# IMU_V1_0.net
KiCad netlist of a schematic drawn in EAGLE
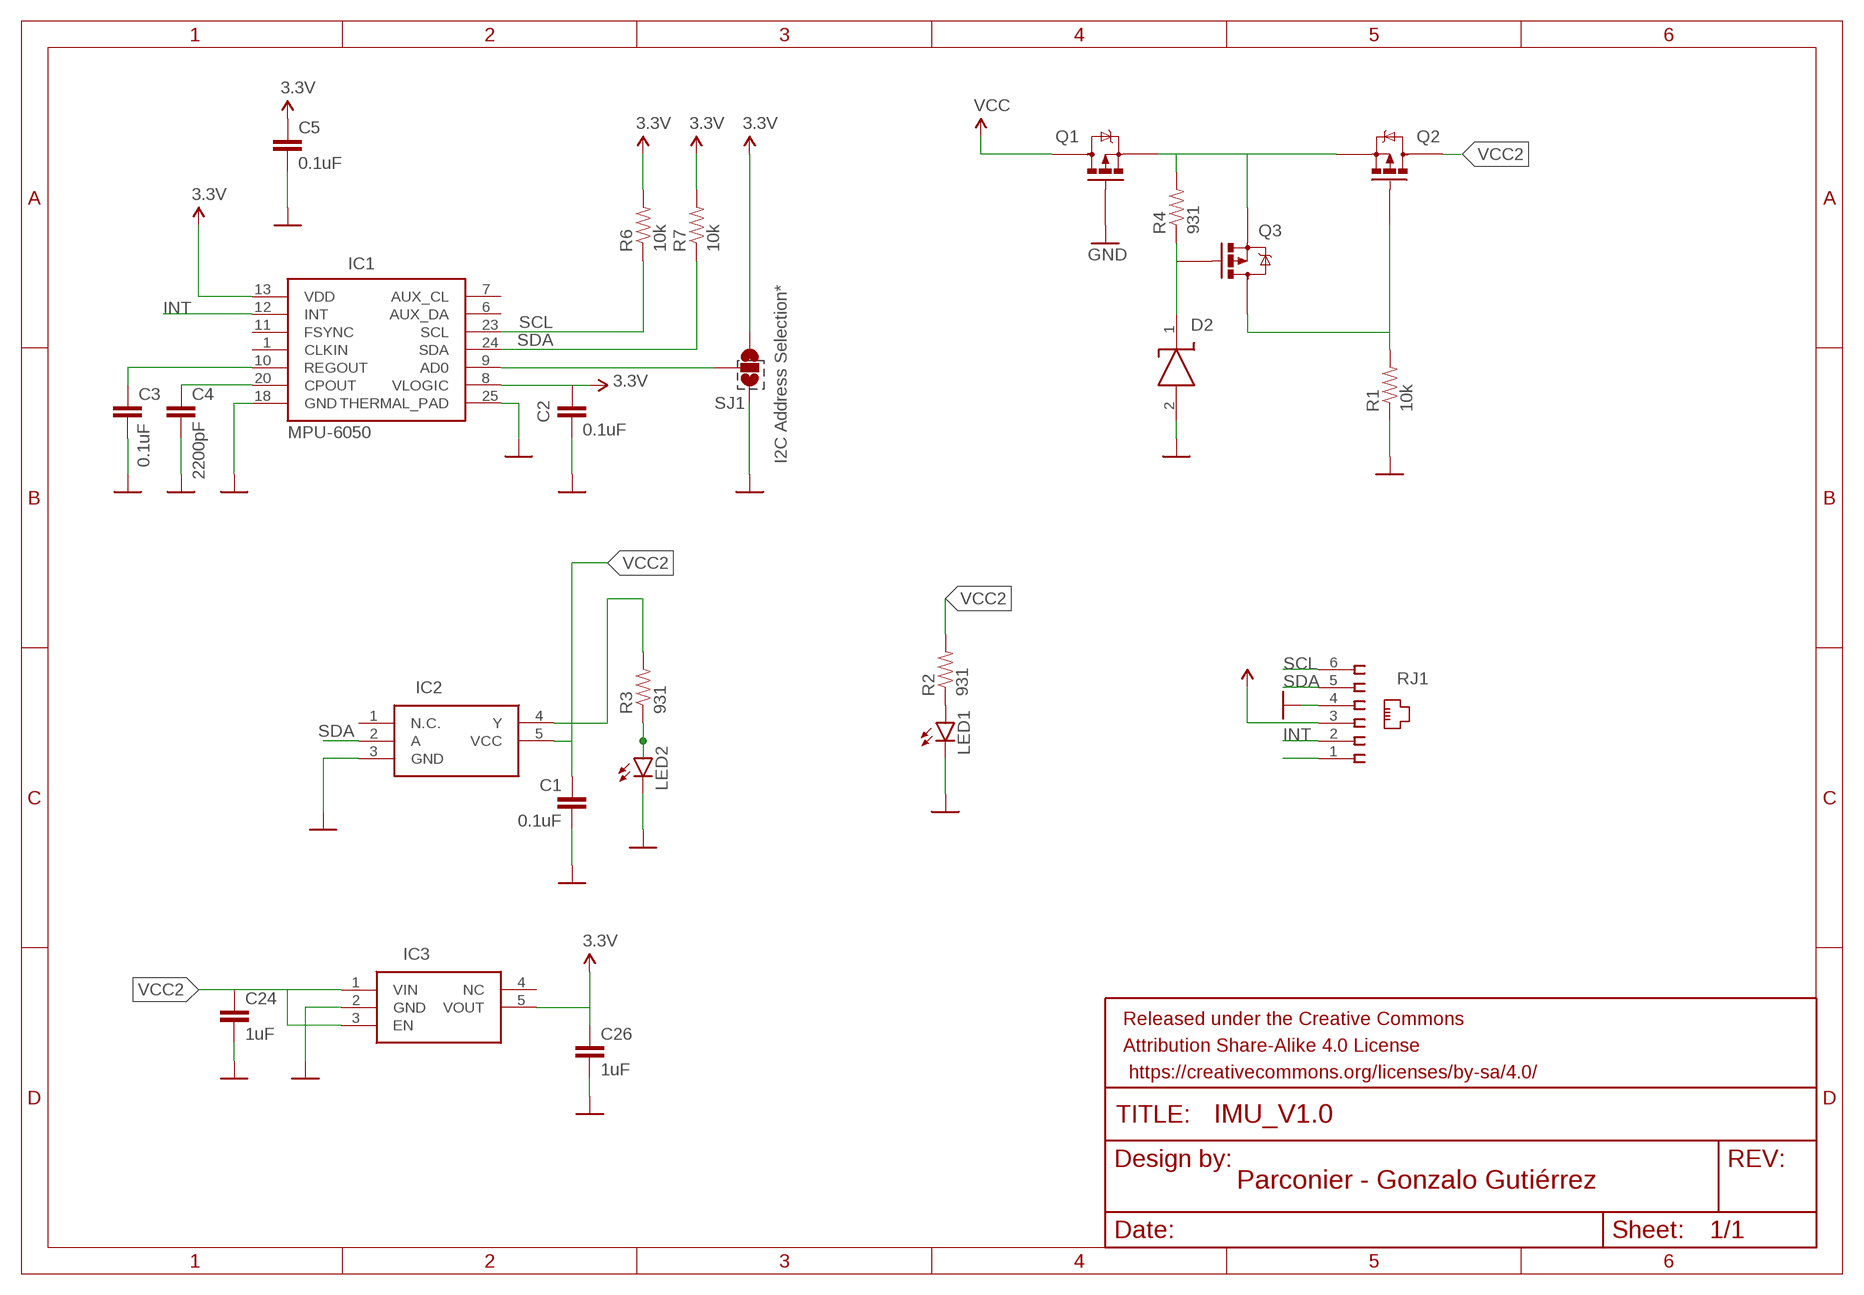
[diagram p0: schematic, sheet 1]

(export (version "E")
  (design (tool "Eeschema 10.0.6"))
  (components
    (comp (ref "C1")
      (value "0.1uF")
      (footprint "eagle-import:0402")
      (fields (field (name "MPN") "CC0402KRX5R9BB104"))
      (libsource (lib "eagle-import") (part "CAP_0402"))
    )
    (comp (ref "C2")
      (value "0.1uF")
      (footprint "eagle-import:0402")
      (fields (field (name "MPN") "CC0402KRX5R9BB104"))
      (libsource (lib "eagle-import") (part "CAP_0402"))
    )
    (comp (ref "C3")
      (value "0.1uF")
      (footprint "eagle-import:0402")
      (fields (field (name "MPN") "CC0402KRX5R9BB104"))
      (libsource (lib "eagle-import") (part "CAP_0402"))
    )
    (comp (ref "C4")
      (value "2200pF")
      (footprint "eagle-import:0402")
      (fields (field (name "MPN") "GRM155R71H222JA01D"))
      (libsource (lib "eagle-import") (part "CAP_0402"))
    )
    (comp (ref "C5")
      (value "0.1uF")
      (footprint "eagle-import:0402")
      (fields (field (name "MPN") "CC0402KRX5R9BB104"))
      (libsource (lib "eagle-import") (part "CAP_0402"))
    )
    (comp (ref "C24")
      (value "1uF")
      (footprint "eagle-import:0402")
      (fields (field (name "MPN") "CC0402ZRY5V6BB105"))
      (libsource (lib "eagle-import") (part "CAP_0402"))
    )
    (comp (ref "C26")
      (value "1uF")
      (footprint "eagle-import:0402")
      (fields (field (name "MPN") "CC0402ZRY5V6BB105"))
      (libsource (lib "eagle-import") (part "CAP_0402"))
    )
    (comp (ref "D2")
      (value "BZT52C5V1-7-F")
      (footprint "eagle-import:SOD3716X145N")
      (fields (field (name "RS_PART_NUMBER") "7384951P"))
      (libsource (lib "eagle-import") (part "BZT52C5V1-7-F"))
    )
    (comp (ref "IC1")
      (value "MPU-6050")
      (footprint "eagle-import:QFN50P400X400X95-25N")
      (fields (field (name "RS_PART_NUMBER") "8837948P"))
      (libsource (lib "eagle-import") (part "MPU-6050"))
    )
    (comp (ref "IC2")
      (value "74LVC1G14GW-Q100,1")
      (footprint "eagle-import:SOT65P212X110-5N")
      (fields (field (name "RS_PART_NUMBER") "1526474") (field (name "MPN") " 74AHC1G14GW-Q100,1"))
      (libsource (lib "eagle-import") (part "74LVC1G14GW-Q100,1"))
    )
    (comp (ref "IC3")
      (value "MIC5504-3.3YM5-TR")
      (footprint "eagle-import:SOT95P280X145-5N")
      (fields (field (name "RS_PART_NUMBER") "9113332"))
      (libsource (lib "eagle-import") (part "MIC5504-3.3YM5-TR"))
    )
    (comp (ref "LED1")
      (value "LED0603")
      (footprint "eagle-import:LED-0603")
      (fields (field (name "MPN") "LTST-C193KRKT-5A"))
      (libsource (lib "eagle-import") (part "LED0603"))
    )
    (comp (ref "LED2")
      (value "LED0603")
      (footprint "eagle-import:LED-0603")
      (fields (field (name "MPN") "LB Q39E-L2OO-35-1 "))
      (libsource (lib "eagle-import") (part "LED0603"))
    )
    (comp (ref "Q1")
      (value "RU1C002ZPTCL")
      (footprint "eagle-import:SOTFL65P210X105-3N")
      (libsource (lib "eagle-import") (part "RU1C002ZPTCL"))
    )
    (comp (ref "Q2")
      (value "RU1C002ZPTCL")
      (footprint "eagle-import:SOTFL65P210X105-3N")
      (description "ROHM - RU1C002ZPTCL - MOSFET, P-CH, -20V, -0.2A, SOT-323FL")
      (fields
        (field (name "ARROW_PART_NUMBER") "RU1C002ZPTCL")
        (field (name "HEIGHT") "1.05mm")
        (field (name "MANUFACTURER_NAME") "ROHM Semiconductor")
        (field (name "MANUFACTURER_PART_NUMBER") "RU1C002ZPTCL")
      )
      (libsource (lib "eagle-import") (part "RU1C002ZPTCL"))
    )
    (comp (ref "Q3")
      (value "RU1C002ZPTCL")
      (footprint "eagle-import:SOTFL65P210X105-3N")
      (description "ROHM - RU1C002ZPTCL - MOSFET, P-CH, -20V, -0.2A, SOT-323FL")
      (fields
        (field (name "ARROW_PART_NUMBER") "RU1C002ZPTCL")
        (field (name "HEIGHT") "1.05mm")
        (field (name "MANUFACTURER_NAME") "ROHM Semiconductor")
        (field (name "MANUFACTURER_PART_NUMBER") "RU1C002ZPTCL")
      )
      (libsource (lib "eagle-import") (part "RU1C002ZPTCL"))
    )
    (comp (ref "R1")
      (value "10k")
      (footprint "eagle-import:RESC1005X35")
      (fields (field (name "MPN") "RC0402JR-7W10KL"))
      (libsource (lib "eagle-import") (part "RES_0402"))
    )
    (comp (ref "R2")
      (value "931")
      (footprint "eagle-import:RESC1005X35")
      (fields (field (name "MPN") "RC0402FR-07931RL"))
      (libsource (lib "eagle-import") (part "RES_0402"))
    )
    (comp (ref "R3")
      (value "931")
      (footprint "eagle-import:RESC1005X35")
      (fields (field (name "MPN") "RC0402FR-07931RL"))
      (libsource (lib "eagle-import") (part "RES_0402"))
    )
    (comp (ref "R4")
      (value "931")
      (footprint "eagle-import:RESC1005X35")
      (fields (field (name "MPN") "RC0402FR-07931RL"))
      (libsource (lib "eagle-import") (part "RES_0402"))
    )
    (comp (ref "R6")
      (value "10k")
      (footprint "eagle-import:RESC1005X35")
      (fields (field (name "MPN") "RC0402JR-7W10KL"))
      (libsource (lib "eagle-import") (part "RES_0402"))
    )
    (comp (ref "R7")
      (value "10k")
      (footprint "eagle-import:RESC1005X35")
      (fields (field (name "MPN") "RC0402JR-7W10KL"))
      (libsource (lib "eagle-import") (part "RES_0402"))
    )
    (comp (ref "RJ1")
      (value "615006138421")
      (footprint "eagle-import:615006138421")
      (fields (field (name "RS_PART_NUMBER") "7350282"))
      (libsource (lib "eagle-import") (part "615006138421"))
    )
    (comp (ref "SJ1")
      (value "SOLDERJUMPER_2WAYPASTE2&3")
      (footprint "eagle-import:SJ_3_PASTE2&3")
      (libsource (lib "eagle-import") (part "SOLDERJUMPER_2WAYPASTE2&3"))
    )
  )
  (nets
    (net (code "1") (name "/INT") (class "Default")
      (node (ref "IC1") (pin "12") (pinfunction "INT_12") (pintype "bidirectional"))
      (node (ref "RJ1") (pin "2") (pinfunction "2_2") (pintype "input"))
    )
    (net (code "2") (name "/SCL") (class "Default")
      (node (ref "IC1") (pin "23") (pinfunction "SCL_23") (pintype "bidirectional"))
      (node (ref "R6") (pin "1") (pinfunction "1_1") (pintype "passive"))
      (node (ref "RJ1") (pin "6") (pinfunction "6_6") (pintype "input"))
    )
    (net (code "3") (name "/SDA") (class "Default")
      (node (ref "IC1") (pin "24") (pinfunction "SDA_24") (pintype "bidirectional"))
      (node (ref "IC2") (pin "2") (pinfunction "A_2") (pintype "bidirectional"))
      (node (ref "R7") (pin "1") (pinfunction "1_1") (pintype "passive"))
      (node (ref "RJ1") (pin "5") (pinfunction "5_5") (pintype "input"))
    )
    (net (code "4") (name "3.3V") (class "Default")
      (node (ref "C2") (pin "1") (pinfunction "1_1") (pintype "passive"))
      (node (ref "C26") (pin "1") (pinfunction "1_1") (pintype "passive"))
      (node (ref "C5") (pin "1") (pinfunction "1_1") (pintype "passive"))
      (node (ref "IC1") (pin "13") (pinfunction "VDD_13") (pintype "bidirectional"))
      (node (ref "IC1") (pin "8") (pinfunction "VLOGIC_8") (pintype "bidirectional"))
      (node (ref "IC3") (pin "5") (pinfunction "VOUT_5") (pintype "input"))
      (node (ref "R6") (pin "2") (pinfunction "2_2") (pintype "passive"))
      (node (ref "R7") (pin "2") (pinfunction "2_2") (pintype "passive"))
      (node (ref "SJ1") (pin "1") (pinfunction "1_1") (pintype "passive"))
    )
    (net (code "5") (name "GND") (class "Default")
      (node (ref "C1") (pin "2") (pinfunction "2_2") (pintype "passive"))
      (node (ref "C2") (pin "2") (pinfunction "2_2") (pintype "passive"))
      (node (ref "C24") (pin "2") (pinfunction "2_2") (pintype "passive"))
      (node (ref "C26") (pin "2") (pinfunction "2_2") (pintype "passive"))
      (node (ref "C3") (pin "2") (pinfunction "2_2") (pintype "passive"))
      (node (ref "C4") (pin "2") (pinfunction "2_2") (pintype "passive"))
      (node (ref "C5") (pin "2") (pinfunction "2_2") (pintype "passive"))
      (node (ref "D2") (pin "2") (pinfunction "A_2") (pintype "bidirectional"))
      (node (ref "IC1") (pin "18") (pinfunction "GND_18") (pintype "bidirectional"))
      (node (ref "IC1") (pin "25") (pinfunction "THERMAL_PAD_25") (pintype "bidirectional"))
      (node (ref "IC2") (pin "3") (pinfunction "GND_3") (pintype "bidirectional"))
      (node (ref "IC3") (pin "2") (pinfunction "GND_2") (pintype "input"))
      (node (ref "LED1") (pin "C") (pinfunction "C_C") (pintype "passive"))
      (node (ref "LED2") (pin "C") (pinfunction "C_C") (pintype "passive"))
      (node (ref "Q1") (pin "1") (pinfunction "G_1") (pintype "bidirectional"))
      (node (ref "R1") (pin "1") (pinfunction "1_1") (pintype "passive"))
      (node (ref "RJ1") (pin "4") (pinfunction "4_4") (pintype "input"))
      (node (ref "SJ1") (pin "3") (pinfunction "3_3") (pintype "passive"))
    )
    (net (code "6") (name "Net-(D2-K)") (class "Default")
      (node (ref "D2") (pin "1") (pinfunction "K_1") (pintype "bidirectional"))
      (node (ref "Q3") (pin "1") (pinfunction "G_1") (pintype "bidirectional"))
      (node (ref "R4") (pin "1") (pinfunction "1_1") (pintype "passive"))
    )
    (net (code "7") (name "Net-(IC1-AD0)") (class "Default")
      (node (ref "IC1") (pin "9") (pinfunction "AD0_9") (pintype "bidirectional"))
      (node (ref "SJ1") (pin "2") (pinfunction "2_2") (pintype "passive"))
    )
    (net (code "8") (name "Net-(IC1-CPOUT)") (class "Default")
      (node (ref "C4") (pin "1") (pinfunction "1_1") (pintype "passive"))
      (node (ref "IC1") (pin "20") (pinfunction "CPOUT_20") (pintype "bidirectional"))
    )
    (net (code "9") (name "Net-(IC1-REGOUT)") (class "Default")
      (node (ref "C3") (pin "1") (pinfunction "1_1") (pintype "passive"))
      (node (ref "IC1") (pin "10") (pinfunction "REGOUT_10") (pintype "bidirectional"))
    )
    (net (code "10") (name "Net-(IC2-Y)") (class "Default")
      (node (ref "IC2") (pin "4") (pinfunction "Y_4") (pintype "bidirectional"))
      (node (ref "R3") (pin "2") (pinfunction "2_2") (pintype "passive"))
    )
    (net (code "11") (name "Net-(LED1-PadA)") (class "Default")
      (node (ref "LED1") (pin "A") (pinfunction "A_A") (pintype "passive"))
      (node (ref "R2") (pin "1") (pinfunction "1_1") (pintype "passive"))
    )
    (net (code "12") (name "Net-(LED2-PadA)") (class "Default")
      (node (ref "LED2") (pin "A") (pinfunction "A_A") (pintype "passive"))
      (node (ref "R3") (pin "1") (pinfunction "1_1") (pintype "passive"))
    )
    (net (code "13") (name "Net-(Q1-S)") (class "Default")
      (node (ref "Q1") (pin "2") (pinfunction "S_2") (pintype "bidirectional"))
      (node (ref "Q2") (pin "2") (pinfunction "S_2") (pintype "bidirectional"))
      (node (ref "Q3") (pin "2") (pinfunction "S_2") (pintype "bidirectional"))
      (node (ref "R4") (pin "2") (pinfunction "2_2") (pintype "passive"))
    )
    (net (code "14") (name "Net-(Q2-G)") (class "Default")
      (node (ref "Q2") (pin "1") (pinfunction "G_1") (pintype "bidirectional"))
      (node (ref "Q3") (pin "3") (pinfunction "D_3") (pintype "bidirectional"))
      (node (ref "R1") (pin "2") (pinfunction "2_2") (pintype "passive"))
    )
    (net (code "15") (name "VCC") (class "Default")
      (node (ref "Q1") (pin "3") (pinfunction "D_3") (pintype "bidirectional"))
      (node (ref "RJ1") (pin "3") (pinfunction "3_3") (pintype "input"))
    )
    (net (code "16") (name "VCC2") (class "Default")
      (node (ref "C1") (pin "1") (pinfunction "1_1") (pintype "passive"))
      (node (ref "C24") (pin "1") (pinfunction "1_1") (pintype "passive"))
      (node (ref "IC2") (pin "5") (pinfunction "VCC_5") (pintype "bidirectional"))
      (node (ref "IC3") (pin "1") (pinfunction "VIN_1") (pintype "input"))
      (node (ref "IC3") (pin "3") (pinfunction "EN_3") (pintype "input"))
      (node (ref "Q2") (pin "3") (pinfunction "D_3") (pintype "bidirectional"))
      (node (ref "R2") (pin "2") (pinfunction "2_2") (pintype "passive"))
    )
    (net (code "17") (name "unconnected-(IC1-AUX_CL-Pad7)") (class "Default")
      (node (ref "IC1") (pin "7") (pinfunction "AUX_CL_7") (pintype "bidirectional"))
    )
    (net (code "18") (name "unconnected-(IC1-AUX_DA-Pad6)") (class "Default")
      (node (ref "IC1") (pin "6") (pinfunction "AUX_DA_6") (pintype "bidirectional"))
    )
    (net (code "19") (name "unconnected-(IC1-CLKIN-Pad1)") (class "Default")
      (node (ref "IC1") (pin "1") (pinfunction "CLKIN_1") (pintype "bidirectional"))
    )
    (net (code "20") (name "unconnected-(IC1-FSYNC-Pad11)") (class "Default")
      (node (ref "IC1") (pin "11") (pinfunction "FSYNC_11") (pintype "bidirectional"))
    )
    (net (code "21") (name "unconnected-(IC2-N.C.-Pad1)") (class "Default")
      (node (ref "IC2") (pin "1") (pinfunction "N.C._1") (pintype "no_connect"))
    )
    (net (code "22") (name "unconnected-(IC3-NC-Pad4)") (class "Default")
      (node (ref "IC3") (pin "4") (pinfunction "NC_4") (pintype "input"))
    )
    (net (code "23") (name "unconnected-(RJ1-Pad1)") (class "Default")
      (node (ref "RJ1") (pin "1") (pinfunction "1_1") (pintype "input"))
    )
  )
)
